# Robot_Psoc.net
KiCad netlist of a schematic drawn in EAGLE
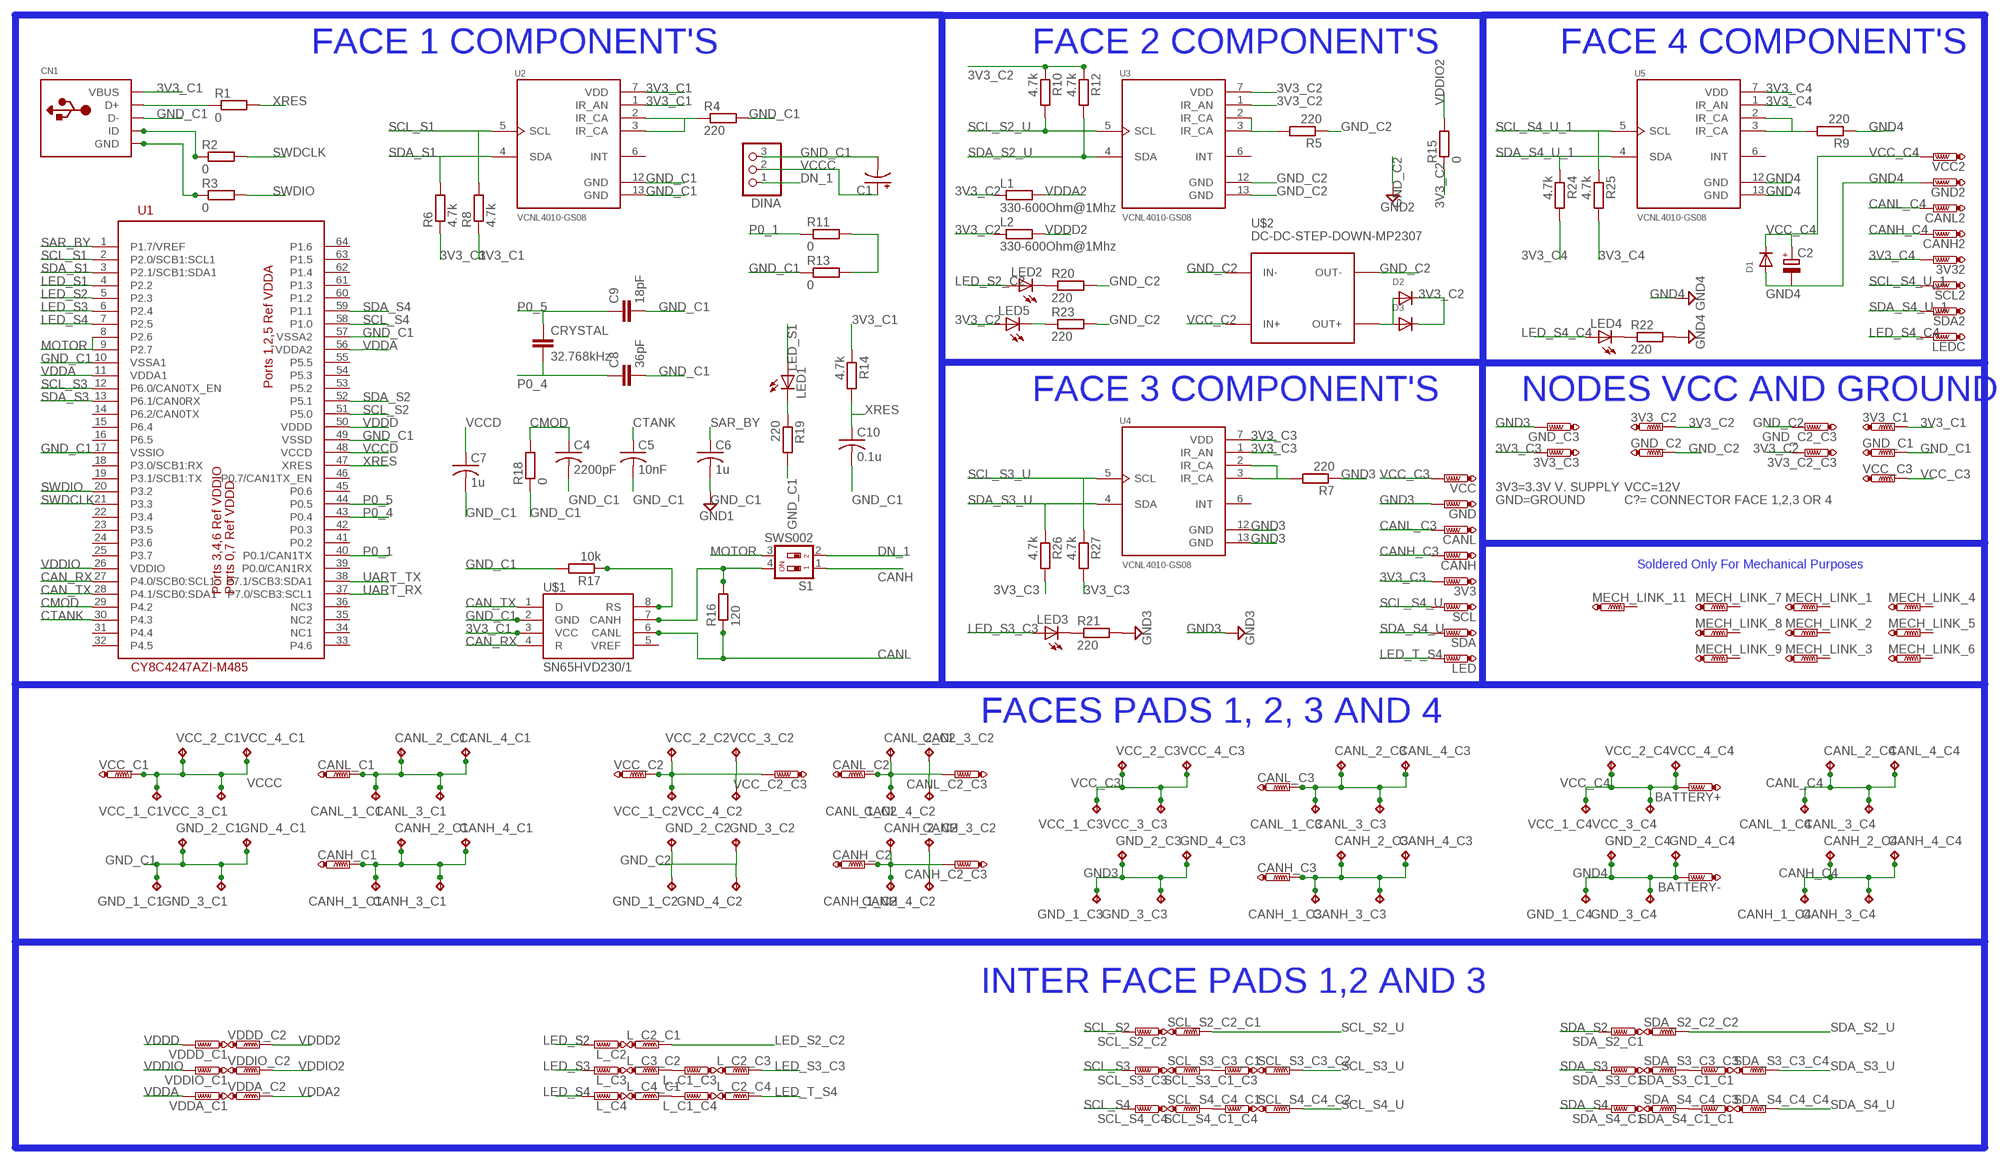
[diagram p0: schematic, sheet 1]

(export (version "E")
  (design (tool "Eeschema 10.0.6"))
  (components
    (comp (ref "3V3")
      (value "PTR1TP11R")
      (footprint "eagle-import:TP11R")
      (libsource (lib "eagle-import") (part "PTR1TP11R"))
    )
    (comp (ref "3V3_C1")
      (value "PTR1TP11R")
      (footprint "eagle-import:TP11R")
      (libsource (lib "eagle-import") (part "PTR1TP11R"))
    )
    (comp (ref "3V3_C2")
      (value "PTR1TP11R")
      (footprint "eagle-import:TP11R")
      (libsource (lib "eagle-import") (part "PTR1TP11R"))
    )
    (comp (ref "3V3_C2_C3")
      (value "PTR1TP11R")
      (footprint "eagle-import:TP11R")
      (libsource (lib "eagle-import") (part "PTR1TP11R"))
    )
    (comp (ref "3V3_C3")
      (value "PTR1TP11R")
      (footprint "eagle-import:TP11R")
      (libsource (lib "eagle-import") (part "PTR1TP11R"))
    )
    (comp (ref "3V32")
      (value "PTR1TP11R")
      (footprint "eagle-import:TP11R")
      (libsource (lib "eagle-import") (part "PTR1TP11R"))
    )
    (comp (ref "BATTERY+")
      (value "PTR1TP11R")
      (footprint "eagle-import:TP11R")
      (libsource (lib "eagle-import") (part "PTR1TP11R"))
    )
    (comp (ref "BATTERY-")
      (value "PTR1TP11R")
      (footprint "eagle-import:TP11R")
      (libsource (lib "eagle-import") (part "PTR1TP11R"))
    )
    (comp (ref "C1")
      (value "CPOL-USUD-5X5,8")
      (footprint "eagle-import:UD-5X5,8_NICHICON")
      (libsource (lib "eagle-import") (part "CPOL-USUD-5X5,8"))
    )
    (comp (ref "C2")
      (value "CPOL-EUUD-8X10")
      (footprint "eagle-import:UD-8X10_NICHICON")
      (libsource (lib "eagle-import") (part "CPOL-EUUD-8X10"))
    )
    (comp (ref "C4")
      (value "2200pF")
      (footprint "eagle-import:C0805")
      (libsource (lib "eagle-import") (part "C-USC0805"))
    )
    (comp (ref "C5")
      (value "10nF")
      (footprint "eagle-import:C0805")
      (libsource (lib "eagle-import") (part "C-USC0805"))
    )
    (comp (ref "C6")
      (value "1u")
      (footprint "eagle-import:C0805")
      (libsource (lib "eagle-import") (part "C-USC0805"))
    )
    (comp (ref "C7")
      (value "1u")
      (footprint "eagle-import:C0805")
      (libsource (lib "eagle-import") (part "C-USC0805"))
    )
    (comp (ref "C8")
      (value "36pF")
      (footprint "eagle-import:C0805")
      (libsource (lib "eagle-import") (part "C-EUC0805"))
    )
    (comp (ref "C9")
      (value "18pF")
      (footprint "eagle-import:C0805")
      (libsource (lib "eagle-import") (part "C-EUC0805"))
    )
    (comp (ref "C10")
      (value "0.1u")
      (footprint "eagle-import:C0805")
      (libsource (lib "eagle-import") (part "C-USC0805"))
    )
    (comp (ref "CANH")
      (value "PTR1TP11R")
      (footprint "eagle-import:TP11R")
      (libsource (lib "eagle-import") (part "PTR1TP11R"))
    )
    (comp (ref "CANH2")
      (value "PTR1TP11R")
      (footprint "eagle-import:TP11R")
      (libsource (lib "eagle-import") (part "PTR1TP11R"))
    )
    (comp (ref "CANH_1_C1")
      (value "TPB2,54")
      (footprint "eagle-import:B2,54")
      (libsource (lib "eagle-import") (part "TPB2,54"))
    )
    (comp (ref "CANH_1_C2")
      (value "TPB2,54")
      (footprint "eagle-import:B2,54")
      (libsource (lib "eagle-import") (part "TPB2,54"))
    )
    (comp (ref "CANH_1_C3")
      (value "TPB2,54")
      (footprint "eagle-import:B2,54")
      (libsource (lib "eagle-import") (part "TPB2,54"))
    )
    (comp (ref "CANH_1_C4")
      (value "TPB2,54")
      (footprint "eagle-import:B2,54")
      (libsource (lib "eagle-import") (part "TPB2,54"))
    )
    (comp (ref "CANH_2_C1")
      (value "TPB2,54")
      (footprint "eagle-import:B2,54")
      (libsource (lib "eagle-import") (part "TPB2,54"))
    )
    (comp (ref "CANH_2_C2")
      (value "TPB2,54")
      (footprint "eagle-import:B2,54")
      (libsource (lib "eagle-import") (part "TPB2,54"))
    )
    (comp (ref "CANH_2_C3")
      (value "TPB2,54")
      (footprint "eagle-import:B2,54")
      (libsource (lib "eagle-import") (part "TPB2,54"))
    )
    (comp (ref "CANH_2_C4")
      (value "TPB2,54")
      (footprint "eagle-import:B2,54")
      (libsource (lib "eagle-import") (part "TPB2,54"))
    )
    (comp (ref "CANH_3_C1")
      (value "TPB2,54")
      (footprint "eagle-import:B2,54")
      (libsource (lib "eagle-import") (part "TPB2,54"))
    )
    (comp (ref "CANH_3_C2")
      (value "TPB2,54")
      (footprint "eagle-import:B2,54")
      (libsource (lib "eagle-import") (part "TPB2,54"))
    )
    (comp (ref "CANH_3_C3")
      (value "TPB2,54")
      (footprint "eagle-import:B2,54")
      (libsource (lib "eagle-import") (part "TPB2,54"))
    )
    (comp (ref "CANH_3_C4")
      (value "TPB2,54")
      (footprint "eagle-import:B2,54")
      (libsource (lib "eagle-import") (part "TPB2,54"))
    )
    (comp (ref "CANH_4_C1")
      (value "TPB2,54")
      (footprint "eagle-import:B2,54")
      (libsource (lib "eagle-import") (part "TPB2,54"))
    )
    (comp (ref "CANH_4_C2")
      (value "TPB2,54")
      (footprint "eagle-import:B2,54")
      (libsource (lib "eagle-import") (part "TPB2,54"))
    )
    (comp (ref "CANH_4_C3")
      (value "TPB2,54")
      (footprint "eagle-import:B2,54")
      (libsource (lib "eagle-import") (part "TPB2,54"))
    )
    (comp (ref "CANH_4_C4")
      (value "TPB2,54")
      (footprint "eagle-import:B2,54")
      (libsource (lib "eagle-import") (part "TPB2,54"))
    )
    (comp (ref "CANH_C1")
      (value "PTR1TP11R")
      (footprint "eagle-import:TP11R")
      (libsource (lib "eagle-import") (part "PTR1TP11R"))
    )
    (comp (ref "CANH_C2")
      (value "PTR1TP11R")
      (footprint "eagle-import:TP11R")
      (libsource (lib "eagle-import") (part "PTR1TP11R"))
    )
    (comp (ref "CANH_C2_C3")
      (value "PTR1TP11R")
      (footprint "eagle-import:TP11R")
      (libsource (lib "eagle-import") (part "PTR1TP11R"))
    )
    (comp (ref "CANH_C3")
      (value "PTR1TP11R")
      (footprint "eagle-import:TP11R")
      (libsource (lib "eagle-import") (part "PTR1TP11R"))
    )
    (comp (ref "CANL")
      (value "PTR1TP11R")
      (footprint "eagle-import:TP11R")
      (libsource (lib "eagle-import") (part "PTR1TP11R"))
    )
    (comp (ref "CANL2")
      (value "PTR1TP11R")
      (footprint "eagle-import:TP11R")
      (libsource (lib "eagle-import") (part "PTR1TP11R"))
    )
    (comp (ref "CANL_1_C1")
      (value "TPB2,54")
      (footprint "eagle-import:B2,54")
      (libsource (lib "eagle-import") (part "TPB2,54"))
    )
    (comp (ref "CANL_1_C2")
      (value "TPB2,54")
      (footprint "eagle-import:B2,54")
      (libsource (lib "eagle-import") (part "TPB2,54"))
    )
    (comp (ref "CANL_1_C3")
      (value "TPB2,54")
      (footprint "eagle-import:B2,54")
      (libsource (lib "eagle-import") (part "TPB2,54"))
    )
    (comp (ref "CANL_1_C4")
      (value "TPB2,54")
      (footprint "eagle-import:B2,54")
      (libsource (lib "eagle-import") (part "TPB2,54"))
    )
    (comp (ref "CANL_2_C1")
      (value "TPB2,54")
      (footprint "eagle-import:B2,54")
      (libsource (lib "eagle-import") (part "TPB2,54"))
    )
    (comp (ref "CANL_2_C2")
      (value "TPB2,54")
      (footprint "eagle-import:B2,54")
      (libsource (lib "eagle-import") (part "TPB2,54"))
    )
    (comp (ref "CANL_2_C3")
      (value "TPB2,54")
      (footprint "eagle-import:B2,54")
      (libsource (lib "eagle-import") (part "TPB2,54"))
    )
    (comp (ref "CANL_2_C4")
      (value "TPB2,54")
      (footprint "eagle-import:B2,54")
      (libsource (lib "eagle-import") (part "TPB2,54"))
    )
    (comp (ref "CANL_3_C1")
      (value "TPB2,54")
      (footprint "eagle-import:B2,54")
      (libsource (lib "eagle-import") (part "TPB2,54"))
    )
    (comp (ref "CANL_3_C2")
      (value "TPB2,54")
      (footprint "eagle-import:B2,54")
      (libsource (lib "eagle-import") (part "TPB2,54"))
    )
    (comp (ref "CANL_3_C3")
      (value "TPB2,54")
      (footprint "eagle-import:B2,54")
      (libsource (lib "eagle-import") (part "TPB2,54"))
    )
    (comp (ref "CANL_3_C4")
      (value "TPB2,54")
      (footprint "eagle-import:B2,54")
      (libsource (lib "eagle-import") (part "TPB2,54"))
    )
    (comp (ref "CANL_4_C1")
      (value "TPB2,54")
      (footprint "eagle-import:B2,54")
      (libsource (lib "eagle-import") (part "TPB2,54"))
    )
    (comp (ref "CANL_4_C2")
      (value "TPB2,54")
      (footprint "eagle-import:B2,54")
      (libsource (lib "eagle-import") (part "TPB2,54"))
    )
    (comp (ref "CANL_4_C3")
      (value "TPB2,54")
      (footprint "eagle-import:B2,54")
      (libsource (lib "eagle-import") (part "TPB2,54"))
    )
    (comp (ref "CANL_4_C4")
      (value "TPB2,54")
      (footprint "eagle-import:B2,54")
      (libsource (lib "eagle-import") (part "TPB2,54"))
    )
    (comp (ref "CANL_C1")
      (value "PTR1TP11R")
      (footprint "eagle-import:TP11R")
      (libsource (lib "eagle-import") (part "PTR1TP11R"))
    )
    (comp (ref "CANL_C2")
      (value "PTR1TP11R")
      (footprint "eagle-import:TP11R")
      (libsource (lib "eagle-import") (part "PTR1TP11R"))
    )
    (comp (ref "CANL_C2_C3")
      (value "PTR1TP11R")
      (footprint "eagle-import:TP11R")
      (libsource (lib "eagle-import") (part "PTR1TP11R"))
    )
    (comp (ref "CANL_C3")
      (value "PTR1TP11R")
      (footprint "eagle-import:TP11R")
      (libsource (lib "eagle-import") (part "PTR1TP11R"))
    )
    (comp (ref "CN1")
      (value "USBMINIB")
      (footprint "eagle-import:USB-MINIB")
      (libsource (lib "eagle-import") (part "USBMINIB"))
    )
    (comp (ref "CRYSTAL")
      (value "32.768kHz")
      (footprint "eagle-import:C0603")
      (libsource (lib "eagle-import") (part "C-EUC0603"))
    )
    (comp (ref "D1")
      (value "DIODESMA")
      (footprint "eagle-import:SMADIODE")
      (libsource (lib "eagle-import") (part "DIODESMA"))
    )
    (comp (ref "D2")
      (value "DIODESOD-123")
      (footprint "eagle-import:SOD-123")
      (libsource (lib "eagle-import") (part "DIODESOD-123"))
    )
    (comp (ref "D3")
      (value "DIODESOD-123")
      (footprint "eagle-import:SOD-123")
      (libsource (lib "eagle-import") (part "DIODESOD-123"))
    )
    (comp (ref "DINA")
      (value "PINHD-1X3")
      (footprint "eagle-import:1X03")
      (libsource (lib "eagle-import") (part "PINHD-1X3"))
    )
    (comp (ref "GND")
      (value "PTR1TP11R")
      (footprint "eagle-import:TP11R")
      (libsource (lib "eagle-import") (part "PTR1TP11R"))
    )
    (comp (ref "GND2")
      (value "PTR1TP11R")
      (footprint "eagle-import:TP11R")
      (libsource (lib "eagle-import") (part "PTR1TP11R"))
    )
    (comp (ref "GND_1_C1")
      (value "TPB2,54")
      (footprint "eagle-import:B2,54")
      (libsource (lib "eagle-import") (part "TPB2,54"))
    )
    (comp (ref "GND_1_C2")
      (value "TPB2,54")
      (footprint "eagle-import:B2,54")
      (libsource (lib "eagle-import") (part "TPB2,54"))
    )
    (comp (ref "GND_1_C3")
      (value "TPB2,54")
      (footprint "eagle-import:B2,54")
      (libsource (lib "eagle-import") (part "TPB2,54"))
    )
    (comp (ref "GND_1_C4")
      (value "TPB2,54")
      (footprint "eagle-import:B2,54")
      (libsource (lib "eagle-import") (part "TPB2,54"))
    )
    (comp (ref "GND_2_C1")
      (value "TPB2,54")
      (footprint "eagle-import:B2,54")
      (libsource (lib "eagle-import") (part "TPB2,54"))
    )
    (comp (ref "GND_2_C2")
      (value "TPB2,54")
      (footprint "eagle-import:B2,54")
      (libsource (lib "eagle-import") (part "TPB2,54"))
    )
    (comp (ref "GND_2_C3")
      (value "TPB2,54")
      (footprint "eagle-import:B2,54")
      (libsource (lib "eagle-import") (part "TPB2,54"))
    )
    (comp (ref "GND_2_C4")
      (value "TPB2,54")
      (footprint "eagle-import:B2,54")
      (libsource (lib "eagle-import") (part "TPB2,54"))
    )
    (comp (ref "GND_3_C1")
      (value "TPB2,54")
      (footprint "eagle-import:B2,54")
      (libsource (lib "eagle-import") (part "TPB2,54"))
    )
    (comp (ref "GND_3_C2")
      (value "TPB2,54")
      (footprint "eagle-import:B2,54")
      (libsource (lib "eagle-import") (part "TPB2,54"))
    )
    (comp (ref "GND_3_C3")
      (value "TPB2,54")
      (footprint "eagle-import:B2,54")
      (libsource (lib "eagle-import") (part "TPB2,54"))
    )
    (comp (ref "GND_3_C4")
      (value "TPB2,54")
      (footprint "eagle-import:B2,54")
      (libsource (lib "eagle-import") (part "TPB2,54"))
    )
    (comp (ref "GND_4_C1")
      (value "TPB2,54")
      (footprint "eagle-import:B2,54")
      (libsource (lib "eagle-import") (part "TPB2,54"))
    )
    (comp (ref "GND_4_C2")
      (value "TPB2,54")
      (footprint "eagle-import:B2,54")
      (libsource (lib "eagle-import") (part "TPB2,54"))
    )
    (comp (ref "GND_4_C3")
      (value "TPB2,54")
      (footprint "eagle-import:B2,54")
      (libsource (lib "eagle-import") (part "TPB2,54"))
    )
    (comp (ref "GND_4_C4")
      (value "TPB2,54")
      (footprint "eagle-import:B2,54")
      (libsource (lib "eagle-import") (part "TPB2,54"))
    )
    (comp (ref "GND_C1")
      (value "PTR1TP11R")
      (footprint "eagle-import:TP11R")
      (libsource (lib "eagle-import") (part "PTR1TP11R"))
    )
    (comp (ref "GND_C2")
      (value "PTR1TP11R")
      (footprint "eagle-import:TP11R")
      (libsource (lib "eagle-import") (part "PTR1TP11R"))
    )
    (comp (ref "GND_C2_C3")
      (value "PTR1TP11R")
      (footprint "eagle-import:TP11R")
      (libsource (lib "eagle-import") (part "PTR1TP11R"))
    )
    (comp (ref "GND_C3")
      (value "PTR1TP11R")
      (footprint "eagle-import:TP11R")
      (libsource (lib "eagle-import") (part "PTR1TP11R"))
    )
    (comp (ref "L1")
      (value "330-600Ohm@1Mhz")
      (footprint "eagle-import:R0805")
      (libsource (lib "eagle-import") (part "R-EU_R0805"))
    )
    (comp (ref "L2")
      (value "330-600Ohm@1Mhz")
      (footprint "eagle-import:R0805")
      (libsource (lib "eagle-import") (part "R-EU_R0805"))
    )
    (comp (ref "LED")
      (value "PTR1TP11R")
      (footprint "eagle-import:TP11R")
      (libsource (lib "eagle-import") (part "PTR1TP11R"))
    )
    (comp (ref "LED1")
      (value "LEDCHIPLED_0805")
      (footprint "eagle-import:CHIPLED_0805")
      (libsource (lib "eagle-import") (part "LEDCHIPLED_0805"))
    )
    (comp (ref "LED2")
      (value "LEDCHIPLED_0805")
      (footprint "eagle-import:CHIPLED_0805")
      (libsource (lib "eagle-import") (part "LEDCHIPLED_0805"))
    )
    (comp (ref "LED3")
      (value "LEDCHIPLED_0805")
      (footprint "eagle-import:CHIPLED_0805")
      (libsource (lib "eagle-import") (part "LEDCHIPLED_0805"))
    )
    (comp (ref "LED4")
      (value "LEDCHIPLED_0805")
      (footprint "eagle-import:CHIPLED_0805")
      (libsource (lib "eagle-import") (part "LEDCHIPLED_0805"))
    )
    (comp (ref "LED5")
      (value "LEDCHIPLED_0805")
      (footprint "eagle-import:CHIPLED_0805")
      (libsource (lib "eagle-import") (part "LEDCHIPLED_0805"))
    )
    (comp (ref "LEDC")
      (value "PTR1TP11R")
      (footprint "eagle-import:TP11R")
      (libsource (lib "eagle-import") (part "PTR1TP11R"))
    )
    (comp (ref "L_C1_C3")
      (value "PTR1TP11R")
      (footprint "eagle-import:TP11R")
      (libsource (lib "eagle-import") (part "PTR1TP11R"))
    )
    (comp (ref "L_C1_C4")
      (value "PTR1TP11R")
      (footprint "eagle-import:TP11R")
      (libsource (lib "eagle-import") (part "PTR1TP11R"))
    )
    (comp (ref "L_C2")
      (value "PTR1TP11R")
      (footprint "eagle-import:TP11R")
      (libsource (lib "eagle-import") (part "PTR1TP11R"))
    )
    (comp (ref "L_C2_C1")
      (value "PTR1TP11R")
      (footprint "eagle-import:TP11R")
      (libsource (lib "eagle-import") (part "PTR1TP11R"))
    )
    (comp (ref "L_C2_C3")
      (value "PTR1TP11R")
      (footprint "eagle-import:TP11R")
      (libsource (lib "eagle-import") (part "PTR1TP11R"))
    )
    (comp (ref "L_C2_C4")
      (value "PTR1TP11R")
      (footprint "eagle-import:TP11R")
      (libsource (lib "eagle-import") (part "PTR1TP11R"))
    )
    (comp (ref "L_C3")
      (value "PTR1TP11R")
      (footprint "eagle-import:TP11R")
      (libsource (lib "eagle-import") (part "PTR1TP11R"))
    )
    (comp (ref "L_C3_C2")
      (value "PTR1TP11R")
      (footprint "eagle-import:TP11R")
      (libsource (lib "eagle-import") (part "PTR1TP11R"))
    )
    (comp (ref "L_C4")
      (value "PTR1TP11R")
      (footprint "eagle-import:TP11R")
      (libsource (lib "eagle-import") (part "PTR1TP11R"))
    )
    (comp (ref "L_C4_C1")
      (value "PTR1TP11R")
      (footprint "eagle-import:TP11R")
      (libsource (lib "eagle-import") (part "PTR1TP11R"))
    )
    (comp (ref "MECH_LINK_1")
      (value "PTR1TP11R")
      (footprint "eagle-import:TP11R")
      (libsource (lib "eagle-import") (part "PTR1TP11R"))
    )
    (comp (ref "MECH_LINK_2")
      (value "PTR1TP11R")
      (footprint "eagle-import:TP11R")
      (libsource (lib "eagle-import") (part "PTR1TP11R"))
    )
    (comp (ref "MECH_LINK_3")
      (value "PTR1TP11R")
      (footprint "eagle-import:TP11R")
      (libsource (lib "eagle-import") (part "PTR1TP11R"))
    )
    (comp (ref "MECH_LINK_4")
      (value "PTR1TP11R")
      (footprint "eagle-import:TP11R")
      (libsource (lib "eagle-import") (part "PTR1TP11R"))
    )
    (comp (ref "MECH_LINK_5")
      (value "PTR1TP11R")
      (footprint "eagle-import:TP11R")
      (libsource (lib "eagle-import") (part "PTR1TP11R"))
    )
    (comp (ref "MECH_LINK_6")
      (value "PTR1TP11R")
      (footprint "eagle-import:TP11R")
      (libsource (lib "eagle-import") (part "PTR1TP11R"))
    )
    (comp (ref "MECH_LINK_7")
      (value "PTR1TP11R")
      (footprint "eagle-import:TP11R")
      (libsource (lib "eagle-import") (part "PTR1TP11R"))
    )
    (comp (ref "MECH_LINK_8")
      (value "PTR1TP11R")
      (footprint "eagle-import:TP11R")
      (libsource (lib "eagle-import") (part "PTR1TP11R"))
    )
    (comp (ref "MECH_LINK_9")
      (value "PTR1TP11R")
      (footprint "eagle-import:TP11R")
      (libsource (lib "eagle-import") (part "PTR1TP11R"))
    )
    (comp (ref "MECH_LINK_11")
      (value "PTR1TP11R")
      (footprint "eagle-import:TP11R")
      (libsource (lib "eagle-import") (part "PTR1TP11R"))
    )
    (comp (ref "R1")
      (value "0")
      (footprint "eagle-import:R0805")
      (libsource (lib "eagle-import") (part "R-EU_R0805"))
    )
    (comp (ref "R2")
      (value "0")
      (footprint "eagle-import:R0805")
      (libsource (lib "eagle-import") (part "R-EU_R0805"))
    )
    (comp (ref "R3")
      (value "0")
      (footprint "eagle-import:R0805")
      (libsource (lib "eagle-import") (part "R-EU_R0805"))
    )
    (comp (ref "R4")
      (value "220")
      (footprint "eagle-import:R0805")
      (libsource (lib "eagle-import") (part "R-EU_R0805"))
    )
    (comp (ref "R5")
      (value "220")
      (footprint "eagle-import:R0805")
      (libsource (lib "eagle-import") (part "R-EU_R0805"))
    )
    (comp (ref "R6")
      (value "4.7k")
      (footprint "eagle-import:R0805")
      (libsource (lib "eagle-import") (part "R-EU_R0805"))
    )
    (comp (ref "R7")
      (value "220")
      (footprint "eagle-import:R0805")
      (libsource (lib "eagle-import") (part "R-EU_R0805"))
    )
    (comp (ref "R8")
      (value "4.7k")
      (footprint "eagle-import:R0805")
      (libsource (lib "eagle-import") (part "R-EU_R0805"))
    )
    (comp (ref "R9")
      (value "220")
      (footprint "eagle-import:R0805")
      (libsource (lib "eagle-import") (part "R-EU_R0805"))
    )
    (comp (ref "R10")
      (value "4.7k")
      (footprint "eagle-import:R0805")
      (libsource (lib "eagle-import") (part "R-EU_R0805"))
    )
    (comp (ref "R11")
      (value "0")
      (footprint "eagle-import:R0805")
      (libsource (lib "eagle-import") (part "R-EU_R0805"))
    )
    (comp (ref "R12")
      (value "4.7k")
      (footprint "eagle-import:R0805")
      (libsource (lib "eagle-import") (part "R-EU_R0805"))
    )
    (comp (ref "R13")
      (value "0")
      (footprint "eagle-import:R0805")
      (libsource (lib "eagle-import") (part "R-EU_R0805"))
    )
    (comp (ref "R14")
      (value "4.7k")
      (footprint "eagle-import:R0805")
      (libsource (lib "eagle-import") (part "R-EU_R0805"))
    )
    (comp (ref "R15")
      (value "0")
      (footprint "eagle-import:R0805")
      (libsource (lib "eagle-import") (part "R-EU_R0805"))
    )
    (comp (ref "R16")
      (value "120")
      (footprint "eagle-import:R0805")
      (libsource (lib "eagle-import") (part "R-EU_R0805"))
    )
    (comp (ref "R17")
      (value "10k")
      (footprint "eagle-import:R0805")
      (libsource (lib "eagle-import") (part "R-EU_R0805"))
    )
    (comp (ref "R18")
      (value "0")
      (footprint "eagle-import:R0805")
      (libsource (lib "eagle-import") (part "R-EU_R0805"))
    )
    (comp (ref "R19")
      (value "220")
      (footprint "eagle-import:R0805")
      (libsource (lib "eagle-import") (part "R-EU_R0805"))
    )
    (comp (ref "R20")
      (value "220")
      (footprint "eagle-import:R0805")
      (libsource (lib "eagle-import") (part "R-EU_R0805"))
    )
    (comp (ref "R21")
      (value "220")
      (footprint "eagle-import:R0805")
      (libsource (lib "eagle-import") (part "R-EU_R0805"))
    )
    (comp (ref "R22")
      (value "220")
      (footprint "eagle-import:R0805")
      (libsource (lib "eagle-import") (part "R-EU_R0805"))
    )
    (comp (ref "R23")
      (value "220")
      (footprint "eagle-import:R0805")
      (libsource (lib "eagle-import") (part "R-EU_R0805"))
    )
    (comp (ref "R24")
      (value "4.7k")
      (footprint "eagle-import:R0805")
      (libsource (lib "eagle-import") (part "R-EU_R0805"))
    )
    (comp (ref "R25")
      (value "4.7k")
      (footprint "eagle-import:R0805")
      (libsource (lib "eagle-import") (part "R-EU_R0805"))
    )
    (comp (ref "R26")
      (value "4.7k")
      (footprint "eagle-import:R0805")
      (libsource (lib "eagle-import") (part "R-EU_R0805"))
    )
    (comp (ref "R27")
      (value "4.7k")
      (footprint "eagle-import:R0805")
      (libsource (lib "eagle-import") (part "R-EU_R0805"))
    )
    (comp (ref "S1")
      (value "SWS002")
      (footprint "eagle-import:SMS-002")
      (libsource (lib "eagle-import") (part "SWS002"))
    )
    (comp (ref "SCL")
      (value "PTR1TP11R")
      (footprint "eagle-import:TP11R")
      (libsource (lib "eagle-import") (part "PTR1TP11R"))
    )
    (comp (ref "SCL2")
      (value "PTR1TP11R")
      (footprint "eagle-import:TP11R")
      (libsource (lib "eagle-import") (part "PTR1TP11R"))
    )
    (comp (ref "SCL_S2_C2")
      (value "PTR1TP11R")
      (footprint "eagle-import:TP11R")
      (libsource (lib "eagle-import") (part "PTR1TP11R"))
    )
    (comp (ref "SCL_S2_C2_C1")
      (value "PTR1TP11R")
      (footprint "eagle-import:TP11R")
      (libsource (lib "eagle-import") (part "PTR1TP11R"))
    )
    (comp (ref "SCL_S3_C1_C3")
      (value "PTR1TP11R")
      (footprint "eagle-import:TP11R")
      (libsource (lib "eagle-import") (part "PTR1TP11R"))
    )
    (comp (ref "SCL_S3_C3")
      (value "PTR1TP11R")
      (footprint "eagle-import:TP11R")
      (libsource (lib "eagle-import") (part "PTR1TP11R"))
    )
    (comp (ref "SCL_S3_C3_C1")
      (value "PTR1TP11R")
      (footprint "eagle-import:TP11R")
      (libsource (lib "eagle-import") (part "PTR1TP11R"))
    )
    (comp (ref "SCL_S3_C3_C2")
      (value "PTR1TP11R")
      (footprint "eagle-import:TP11R")
      (libsource (lib "eagle-import") (part "PTR1TP11R"))
    )
    (comp (ref "SCL_S4_C1_C4")
      (value "PTR1TP11R")
      (footprint "eagle-import:TP11R")
      (libsource (lib "eagle-import") (part "PTR1TP11R"))
    )
    (comp (ref "SCL_S4_C4")
      (value "PTR1TP11R")
      (footprint "eagle-import:TP11R")
      (libsource (lib "eagle-import") (part "PTR1TP11R"))
    )
    (comp (ref "SCL_S4_C4_C1")
      (value "PTR1TP11R")
      (footprint "eagle-import:TP11R")
      (libsource (lib "eagle-import") (part "PTR1TP11R"))
    )
    (comp (ref "SCL_S4_C4_C2")
      (value "PTR1TP11R")
      (footprint "eagle-import:TP11R")
      (libsource (lib "eagle-import") (part "PTR1TP11R"))
    )
    (comp (ref "SDA")
      (value "PTR1TP11R")
      (footprint "eagle-import:TP11R")
      (libsource (lib "eagle-import") (part "PTR1TP11R"))
    )
    (comp (ref "SDA2")
      (value "PTR1TP11R")
      (footprint "eagle-import:TP11R")
      (libsource (lib "eagle-import") (part "PTR1TP11R"))
    )
    (comp (ref "SDA_S2_C1")
      (value "PTR1TP11R")
      (footprint "eagle-import:TP11R")
      (libsource (lib "eagle-import") (part "PTR1TP11R"))
    )
    (comp (ref "SDA_S2_C2_C2")
      (value "PTR1TP11R")
      (footprint "eagle-import:TP11R")
      (libsource (lib "eagle-import") (part "PTR1TP11R"))
    )
    (comp (ref "SDA_S3_C1")
      (value "PTR1TP11R")
      (footprint "eagle-import:TP11R")
      (libsource (lib "eagle-import") (part "PTR1TP11R"))
    )
    (comp (ref "SDA_S3_C1_C1")
      (value "PTR1TP11R")
      (footprint "eagle-import:TP11R")
      (libsource (lib "eagle-import") (part "PTR1TP11R"))
    )
    (comp (ref "SDA_S3_C3_C3")
      (value "PTR1TP11R")
      (footprint "eagle-import:TP11R")
      (libsource (lib "eagle-import") (part "PTR1TP11R"))
    )
    (comp (ref "SDA_S3_C3_C4")
      (value "PTR1TP11R")
      (footprint "eagle-import:TP11R")
      (libsource (lib "eagle-import") (part "PTR1TP11R"))
    )
    (comp (ref "SDA_S4_C1")
      (value "PTR1TP11R")
      (footprint "eagle-import:TP11R")
      (libsource (lib "eagle-import") (part "PTR1TP11R"))
    )
    (comp (ref "SDA_S4_C1_C1")
      (value "PTR1TP11R")
      (footprint "eagle-import:TP11R")
      (libsource (lib "eagle-import") (part "PTR1TP11R"))
    )
    (comp (ref "SDA_S4_C4_C3")
      (value "PTR1TP11R")
      (footprint "eagle-import:TP11R")
      (libsource (lib "eagle-import") (part "PTR1TP11R"))
    )
    (comp (ref "SDA_S4_C4_C4")
      (value "PTR1TP11R")
      (footprint "eagle-import:TP11R")
      (libsource (lib "eagle-import") (part "PTR1TP11R"))
    )
    (comp (ref "U$1")
      (value "SN65HVD230/1")
      (footprint "eagle-import:SO8")
      (libsource (lib "eagle-import") (part "SN65HVD230/1"))
    )
    (comp (ref "U$2")
      (value "DC-DC-STEP-DOWN-MP2307")
      (footprint "eagle-import:DC-DC-STEP-DOWN-MP2307")
      (libsource (lib "eagle-import") (part "DC-DC-STEP-DOWN-MP2307"))
    )
    (comp (ref "U1")
      (value "CY8C4247AZI-M485")
      (footprint "eagle-import:TQFP64-10X10")
      (libsource (lib "eagle-import") (part "CY8C4247AZI-M485"))
    )
    (comp (ref "U2")
      (value "VCNL4010-GS08")
      (footprint "eagle-import:XDCR_VCNL4010-GS08")
      (libsource (lib "eagle-import") (part "VCNL4010-GS08"))
    )
    (comp (ref "U3")
      (value "VCNL4010-GS08")
      (footprint "eagle-import:XDCR_VCNL4010-GS08")
      (libsource (lib "eagle-import") (part "VCNL4010-GS08"))
    )
    (comp (ref "U4")
      (value "VCNL4010-GS08")
      (footprint "eagle-import:XDCR_VCNL4010-GS08")
      (libsource (lib "eagle-import") (part "VCNL4010-GS08"))
    )
    (comp (ref "U5")
      (value "VCNL4010-GS08")
      (footprint "eagle-import:XDCR_VCNL4010-GS08")
      (libsource (lib "eagle-import") (part "VCNL4010-GS08"))
    )
    (comp (ref "VCC")
      (value "PTR1TP11R")
      (footprint "eagle-import:TP11R")
      (libsource (lib "eagle-import") (part "PTR1TP11R"))
    )
    (comp (ref "VCC2")
      (value "PTR1TP11R")
      (footprint "eagle-import:TP11R")
      (libsource (lib "eagle-import") (part "PTR1TP11R"))
    )
    (comp (ref "VCC_1_C1")
      (value "TPB2,54")
      (footprint "eagle-import:B2,54")
      (libsource (lib "eagle-import") (part "TPB2,54"))
    )
    (comp (ref "VCC_1_C2")
      (value "TPB2,54")
      (footprint "eagle-import:B2,54")
      (libsource (lib "eagle-import") (part "TPB2,54"))
    )
    (comp (ref "VCC_1_C3")
      (value "TPB2,54")
      (footprint "eagle-import:B2,54")
      (libsource (lib "eagle-import") (part "TPB2,54"))
    )
    (comp (ref "VCC_1_C4")
      (value "TPB2,54")
      (footprint "eagle-import:B2,54")
      (libsource (lib "eagle-import") (part "TPB2,54"))
    )
    (comp (ref "VCC_2_C1")
      (value "TPB2,54")
      (footprint "eagle-import:B2,54")
      (libsource (lib "eagle-import") (part "TPB2,54"))
    )
    (comp (ref "VCC_2_C2")
      (value "TPB2,54")
      (footprint "eagle-import:B2,54")
      (libsource (lib "eagle-import") (part "TPB2,54"))
    )
    (comp (ref "VCC_2_C3")
      (value "TPB2,54")
      (footprint "eagle-import:B2,54")
      (libsource (lib "eagle-import") (part "TPB2,54"))
    )
    (comp (ref "VCC_2_C4")
      (value "TPB2,54")
      (footprint "eagle-import:B2,54")
      (libsource (lib "eagle-import") (part "TPB2,54"))
    )
    (comp (ref "VCC_3_C1")
      (value "TPB2,54")
      (footprint "eagle-import:B2,54")
      (libsource (lib "eagle-import") (part "TPB2,54"))
    )
    (comp (ref "VCC_3_C2")
      (value "TPB2,54")
      (footprint "eagle-import:B2,54")
      (libsource (lib "eagle-import") (part "TPB2,54"))
    )
    (comp (ref "VCC_3_C3")
      (value "TPB2,54")
      (footprint "eagle-import:B2,54")
      (libsource (lib "eagle-import") (part "TPB2,54"))
    )
    (comp (ref "VCC_3_C4")
      (value "TPB2,54")
      (footprint "eagle-import:B2,54")
      (libsource (lib "eagle-import") (part "TPB2,54"))
    )
    (comp (ref "VCC_4_C1")
      (value "TPB2,54")
      (footprint "eagle-import:B2,54")
      (libsource (lib "eagle-import") (part "TPB2,54"))
    )
    (comp (ref "VCC_4_C2")
      (value "TPB2,54")
      (footprint "eagle-import:B2,54")
      (libsource (lib "eagle-import") (part "TPB2,54"))
    )
    (comp (ref "VCC_4_C3")
      (value "TPB2,54")
      (footprint "eagle-import:B2,54")
      (libsource (lib "eagle-import") (part "TPB2,54"))
    )
    (comp (ref "VCC_4_C4")
      (value "TPB2,54")
      (footprint "eagle-import:B2,54")
      (libsource (lib "eagle-import") (part "TPB2,54"))
    )
    (comp (ref "VCC_C1")
      (value "PTR1TP11R")
      (footprint "eagle-import:TP11R")
      (libsource (lib "eagle-import") (part "PTR1TP11R"))
    )
    (comp (ref "VCC_C2")
      (value "PTR1TP11R")
      (footprint "eagle-import:TP11R")
      (libsource (lib "eagle-import") (part "PTR1TP11R"))
    )
    (comp (ref "VCC_C2_C3")
      (value "PTR1TP11R")
      (footprint "eagle-import:TP11R")
      (libsource (lib "eagle-import") (part "PTR1TP11R"))
    )
    (comp (ref "VCC_C3")
      (value "PTR1TP11R")
      (footprint "eagle-import:TP11R")
      (libsource (lib "eagle-import") (part "PTR1TP11R"))
    )
    (comp (ref "VDDA_C1")
      (value "PTR1TP11R")
      (footprint "eagle-import:TP11R")
      (libsource (lib "eagle-import") (part "PTR1TP11R"))
    )
    (comp (ref "VDDA_C2")
      (value "PTR1TP11R")
      (footprint "eagle-import:TP11R")
      (libsource (lib "eagle-import") (part "PTR1TP11R"))
    )
    (comp (ref "VDDD_C1")
      (value "PTR1TP11R")
      (footprint "eagle-import:TP11R")
      (libsource (lib "eagle-import") (part "PTR1TP11R"))
    )
    (comp (ref "VDDD_C2")
      (value "PTR1TP11R")
      (footprint "eagle-import:TP11R")
      (libsource (lib "eagle-import") (part "PTR1TP11R"))
    )
    (comp (ref "VDDIO_C1")
      (value "PTR1TP11R")
      (footprint "eagle-import:TP11R")
      (libsource (lib "eagle-import") (part "PTR1TP11R"))
    )
    (comp (ref "VDDIO_C2")
      (value "PTR1TP11R")
      (footprint "eagle-import:TP11R")
      (libsource (lib "eagle-import") (part "PTR1TP11R"))
    )
  )
  (nets
    (net (code "1") (name "/3V3_C1") (class "Default")
      (node (ref "3V3_C1") (pin "TP") (pinfunction "TP_TP") (pintype "input"))
      (node (ref "CN1") (pin "VBUS") (pinfunction "VBUS_VBUS") (pintype "power_in"))
      (node (ref "R14") (pin "1") (pinfunction "1_1") (pintype "passive"))
      (node (ref "R6") (pin "1") (pinfunction "1_1") (pintype "passive"))
      (node (ref "R8") (pin "1") (pinfunction "1_1") (pintype "passive"))
      (node (ref "U$1") (pin "3") (pinfunction "VCC_3") (pintype "power_in"))
      (node (ref "U2") (pin "1") (pinfunction "IR_AN_1") (pintype "power_in"))
      (node (ref "U2") (pin "7") (pinfunction "VDD_7") (pintype "power_in"))
    )
    (net (code "2") (name "/3V3_C2") (class "Default")
      (node (ref "3V3_C2") (pin "TP") (pinfunction "TP_TP") (pintype "input"))
      (node (ref "3V3_C2_C3") (pin "TP") (pinfunction "TP_TP") (pintype "input"))
      (node (ref "D2") (pin "C") (pinfunction "C_C") (pintype "passive"))
      (node (ref "D3") (pin "C") (pinfunction "C_C") (pintype "passive"))
      (node (ref "L1") (pin "1") (pinfunction "1_1") (pintype "passive"))
      (node (ref "L2") (pin "1") (pinfunction "1_1") (pintype "passive"))
      (node (ref "LED5") (pin "A") (pinfunction "A_A") (pintype "passive"))
      (node (ref "R10") (pin "1") (pinfunction "1_1") (pintype "passive"))
      (node (ref "R12") (pin "1") (pinfunction "1_1") (pintype "passive"))
      (node (ref "R15") (pin "1") (pinfunction "1_1") (pintype "passive"))
      (node (ref "U3") (pin "1") (pinfunction "IR_AN_1") (pintype "power_in"))
      (node (ref "U3") (pin "7") (pinfunction "VDD_7") (pintype "power_in"))
    )
    (net (code "3") (name "/3V3_C3") (class "Default")
      (node (ref "3V3") (pin "TP") (pinfunction "TP_TP") (pintype "input"))
      (node (ref "3V3_C3") (pin "TP") (pinfunction "TP_TP") (pintype "input"))
      (node (ref "R26") (pin "2") (pinfunction "2_2") (pintype "passive"))
      (node (ref "R27") (pin "2") (pinfunction "2_2") (pintype "passive"))
      (node (ref "U4") (pin "1") (pinfunction "IR_AN_1") (pintype "power_in"))
      (node (ref "U4") (pin "7") (pinfunction "VDD_7") (pintype "power_in"))
    )
    (net (code "4") (name "/3V3_C4") (class "Default")
      (node (ref "3V32") (pin "TP") (pinfunction "TP_TP") (pintype "input"))
      (node (ref "R24") (pin "2") (pinfunction "2_2") (pintype "passive"))
      (node (ref "R25") (pin "2") (pinfunction "2_2") (pintype "passive"))
      (node (ref "U5") (pin "1") (pinfunction "IR_AN_1") (pintype "power_in"))
      (node (ref "U5") (pin "7") (pinfunction "VDD_7") (pintype "power_in"))
    )
    (net (code "5") (name "/CANH") (class "Default")
      (node (ref "CANH_1_C1") (pin "TP") (pinfunction "TP_TP") (pintype "input"))
      (node (ref "CANH_2_C1") (pin "TP") (pinfunction "TP_TP") (pintype "input"))
      (node (ref "CANH_3_C1") (pin "TP") (pinfunction "TP_TP") (pintype "input"))
      (node (ref "CANH_4_C1") (pin "TP") (pinfunction "TP_TP") (pintype "input"))
      (node (ref "CANH_C1") (pin "TP") (pinfunction "TP_TP") (pintype "input"))
      (node (ref "S1") (pin "1") (pinfunction "1_1") (pintype "passive"))
    )
    (net (code "6") (name "/CANH_C3") (class "Default")
      (node (ref "CANH") (pin "TP") (pinfunction "TP_TP") (pintype "input"))
      (node (ref "CANH_1_C3") (pin "TP") (pinfunction "TP_TP") (pintype "input"))
      (node (ref "CANH_2_C3") (pin "TP") (pinfunction "TP_TP") (pintype "input"))
      (node (ref "CANH_3_C3") (pin "TP") (pinfunction "TP_TP") (pintype "input"))
      (node (ref "CANH_4_C3") (pin "TP") (pinfunction "TP_TP") (pintype "input"))
      (node (ref "CANH_C3") (pin "TP") (pinfunction "TP_TP") (pintype "input"))
    )
    (net (code "7") (name "/CANH_C4") (class "Default")
      (node (ref "CANH2") (pin "TP") (pinfunction "TP_TP") (pintype "input"))
      (node (ref "CANH_1_C4") (pin "TP") (pinfunction "TP_TP") (pintype "input"))
      (node (ref "CANH_2_C4") (pin "TP") (pinfunction "TP_TP") (pintype "input"))
      (node (ref "CANH_3_C4") (pin "TP") (pinfunction "TP_TP") (pintype "input"))
      (node (ref "CANH_4_C4") (pin "TP") (pinfunction "TP_TP") (pintype "input"))
    )
    (net (code "8") (name "/CANL") (class "Default")
      (node (ref "CANL_1_C1") (pin "TP") (pinfunction "TP_TP") (pintype "input"))
      (node (ref "CANL_2_C1") (pin "TP") (pinfunction "TP_TP") (pintype "input"))
      (node (ref "CANL_3_C1") (pin "TP") (pinfunction "TP_TP") (pintype "input"))
      (node (ref "CANL_4_C1") (pin "TP") (pinfunction "TP_TP") (pintype "input"))
      (node (ref "CANL_C1") (pin "TP") (pinfunction "TP_TP") (pintype "input"))
      (node (ref "R16") (pin "1") (pinfunction "1_1") (pintype "passive"))
      (node (ref "U$1") (pin "6") (pinfunction "CANL_6") (pintype "bidirectional"))
    )
    (net (code "9") (name "/CANL_C3") (class "Default")
      (node (ref "CANL") (pin "TP") (pinfunction "TP_TP") (pintype "input"))
      (node (ref "CANL_1_C3") (pin "TP") (pinfunction "TP_TP") (pintype "input"))
      (node (ref "CANL_2_C3") (pin "TP") (pinfunction "TP_TP") (pintype "input"))
      (node (ref "CANL_3_C3") (pin "TP") (pinfunction "TP_TP") (pintype "input"))
      (node (ref "CANL_4_C3") (pin "TP") (pinfunction "TP_TP") (pintype "input"))
      (node (ref "CANL_C3") (pin "TP") (pinfunction "TP_TP") (pintype "input"))
    )
    (net (code "10") (name "/CANL_C4") (class "Default")
      (node (ref "CANL2") (pin "TP") (pinfunction "TP_TP") (pintype "input"))
      (node (ref "CANL_1_C4") (pin "TP") (pinfunction "TP_TP") (pintype "input"))
      (node (ref "CANL_2_C4") (pin "TP") (pinfunction "TP_TP") (pintype "input"))
      (node (ref "CANL_3_C4") (pin "TP") (pinfunction "TP_TP") (pintype "input"))
      (node (ref "CANL_4_C4") (pin "TP") (pinfunction "TP_TP") (pintype "input"))
    )
    (net (code "11") (name "/CAN_RX") (class "Default")
      (node (ref "U$1") (pin "4") (pinfunction "R_4") (pintype "bidirectional"))
      (node (ref "U1") (pin "27") (pinfunction "P4.0/SCB0:SCL1_27") (pintype "bidirectional"))
    )
    (net (code "12") (name "/CAN_TX") (class "Default")
      (node (ref "U$1") (pin "1") (pinfunction "D_1") (pintype "bidirectional"))
      (node (ref "U1") (pin "28") (pinfunction "P4.1/SCB0:SDA1_28") (pintype "bidirectional"))
    )
    (net (code "13") (name "/CMOD") (class "Default")
      (node (ref "C4") (pin "1") (pinfunction "1_1") (pintype "passive"))
      (node (ref "R18") (pin "2") (pinfunction "2_2") (pintype "passive"))
      (node (ref "U1") (pin "29") (pinfunction "P4.2_29") (pintype "bidirectional"))
    )
    (net (code "14") (name "/CTANK") (class "Default")
      (node (ref "C5") (pin "1") (pinfunction "1_1") (pintype "passive"))
      (node (ref "U1") (pin "30") (pinfunction "P4.3_30") (pintype "bidirectional"))
    )
    (net (code "15") (name "/DN_1") (class "Default")
      (node (ref "DINA") (pin "1") (pinfunction "1_1") (pintype "passive"))
      (node (ref "S1") (pin "2") (pinfunction "2_2") (pintype "passive"))
    )
    (net (code "16") (name "/LED_S1") (class "Default")
      (node (ref "LED1") (pin "A") (pinfunction "A_A") (pintype "passive"))
      (node (ref "U1") (pin "4") (pinfunction "P2.2_4") (pintype "bidirectional"))
    )
    (net (code "17") (name "/LED_S2") (class "Default")
      (node (ref "L_C2") (pin "TP") (pinfunction "TP_TP") (pintype "input"))
      (node (ref "U1") (pin "5") (pinfunction "P2.3_5") (pintype "bidirectional"))
    )
    (net (code "18") (name "/LED_S2_C2") (class "Default")
      (node (ref "LED2") (pin "A") (pinfunction "A_A") (pintype "passive"))
      (node (ref "L_C2_C1") (pin "TP") (pinfunction "TP_TP") (pintype "input"))
    )
    (net (code "19") (name "/LED_S3") (class "Default")
      (node (ref "L_C3") (pin "TP") (pinfunction "TP_TP") (pintype "input"))
      (node (ref "U1") (pin "6") (pinfunction "P2.4_6") (pintype "bidirectional"))
    )
    (net (code "20") (name "/LED_S3_C3") (class "Default")
      (node (ref "LED3") (pin "A") (pinfunction "A_A") (pintype "passive"))
      (node (ref "L_C2_C3") (pin "TP") (pinfunction "TP_TP") (pintype "input"))
    )
    (net (code "21") (name "/LED_S4") (class "Default")
      (node (ref "L_C4") (pin "TP") (pinfunction "TP_TP") (pintype "input"))
      (node (ref "U1") (pin "7") (pinfunction "P2.5_7") (pintype "bidirectional"))
    )
    (net (code "22") (name "/LED_S4_C4") (class "Default")
      (node (ref "LED4") (pin "A") (pinfunction "A_A") (pintype "passive"))
      (node (ref "LEDC") (pin "TP") (pinfunction "TP_TP") (pintype "input"))
    )
    (net (code "23") (name "/LED_T_S4") (class "Default")
      (node (ref "LED") (pin "TP") (pinfunction "TP_TP") (pintype "input"))
      (node (ref "L_C2_C4") (pin "TP") (pinfunction "TP_TP") (pintype "input"))
    )
    (net (code "24") (name "/MOTOR") (class "Default")
      (node (ref "S1") (pin "3") (pinfunction "3_3") (pintype "passive"))
      (node (ref "U1") (pin "8") (pinfunction "P2.6_8") (pintype "bidirectional"))
      (node (ref "U1") (pin "9") (pinfunction "P2.7_9") (pintype "bidirectional"))
    )
    (net (code "25") (name "/P0_1") (class "Default")
      (node (ref "R11") (pin "1") (pinfunction "1_1") (pintype "passive"))
      (node (ref "U1") (pin "40") (pinfunction "P0.1/CAN1TX_40") (pintype "bidirectional"))
    )
    (net (code "26") (name "/P0_4") (class "Default")
      (node (ref "C8") (pin "1") (pinfunction "1_1") (pintype "passive"))
      (node (ref "CRYSTAL") (pin "2") (pinfunction "2_2") (pintype "passive"))
      (node (ref "U1") (pin "43") (pinfunction "P0.4_43") (pintype "bidirectional"))
    )
    (net (code "27") (name "/P0_5") (class "Default")
      (node (ref "C9") (pin "1") (pinfunction "1_1") (pintype "passive"))
      (node (ref "CRYSTAL") (pin "1") (pinfunction "1_1") (pintype "passive"))
      (node (ref "U1") (pin "44") (pinfunction "P0.5_44") (pintype "bidirectional"))
    )
    (net (code "28") (name "/SAR_BY") (class "Default")
      (node (ref "C6") (pin "1") (pinfunction "1_1") (pintype "passive"))
      (node (ref "U1") (pin "1") (pinfunction "P1.7/VREF_1") (pintype "bidirectional"))
    )
    (net (code "29") (name "/SCL_S1") (class "Default")
      (node (ref "R8") (pin "2") (pinfunction "2_2") (pintype "passive"))
      (node (ref "U1") (pin "2") (pinfunction "P2.0/SCB1:SCL1_2") (pintype "bidirectional"))
      (node (ref "U2") (pin "5") (pinfunction "SCL_5") (pintype "input"))
    )
    (net (code "30") (name "/SCL_S2") (class "Default")
      (node (ref "SCL_S2_C2") (pin "TP") (pinfunction "TP_TP") (pintype "input"))
      (node (ref "U1") (pin "51") (pinfunction "P5.0_51") (pintype "bidirectional"))
    )
    (net (code "31") (name "/SCL_S2_U") (class "Default")
      (node (ref "R10") (pin "2") (pinfunction "2_2") (pintype "passive"))
      (node (ref "SCL_S2_C2_C1") (pin "TP") (pinfunction "TP_TP") (pintype "input"))
      (node (ref "U3") (pin "5") (pinfunction "SCL_5") (pintype "input"))
    )
    (net (code "32") (name "/SCL_S3") (class "Default")
      (node (ref "SCL_S3_C3") (pin "TP") (pinfunction "TP_TP") (pintype "input"))
      (node (ref "U1") (pin "12") (pinfunction "P6.0/CAN0TX_EN_12") (pintype "bidirectional"))
    )
    (net (code "33") (name "/SCL_S3_U") (class "Default")
      (node (ref "R27") (pin "1") (pinfunction "1_1") (pintype "passive"))
      (node (ref "SCL_S3_C3_C2") (pin "TP") (pinfunction "TP_TP") (pintype "input"))
      (node (ref "U4") (pin "5") (pinfunction "SCL_5") (pintype "input"))
    )
    (net (code "34") (name "/SCL_S4") (class "Default")
      (node (ref "SCL_S4_C4") (pin "TP") (pinfunction "TP_TP") (pintype "input"))
      (node (ref "U1") (pin "58") (pinfunction "P1.0_58") (pintype "bidirectional"))
    )
    (net (code "35") (name "/SCL_S4_U") (class "Default")
      (node (ref "SCL") (pin "TP") (pinfunction "TP_TP") (pintype "input"))
      (node (ref "SCL_S4_C4_C2") (pin "TP") (pinfunction "TP_TP") (pintype "input"))
    )
    (net (code "36") (name "/SCL_S4_U_1") (class "Default")
      (node (ref "R25") (pin "1") (pinfunction "1_1") (pintype "passive"))
      (node (ref "SCL2") (pin "TP") (pinfunction "TP_TP") (pintype "input"))
      (node (ref "U5") (pin "5") (pinfunction "SCL_5") (pintype "input"))
    )
    (net (code "37") (name "/SDA_S1") (class "Default")
      (node (ref "R6") (pin "2") (pinfunction "2_2") (pintype "passive"))
      (node (ref "U1") (pin "3") (pinfunction "P2.1/SCB1:SDA1_3") (pintype "bidirectional"))
      (node (ref "U2") (pin "4") (pinfunction "SDA_4") (pintype "bidirectional"))
    )
    (net (code "38") (name "/SDA_S2") (class "Default")
      (node (ref "SDA_S2_C1") (pin "TP") (pinfunction "TP_TP") (pintype "input"))
      (node (ref "U1") (pin "52") (pinfunction "P5.1_52") (pintype "bidirectional"))
    )
    (net (code "39") (name "/SDA_S2_U") (class "Default")
      (node (ref "R12") (pin "2") (pinfunction "2_2") (pintype "passive"))
      (node (ref "SDA_S2_C2_C2") (pin "TP") (pinfunction "TP_TP") (pintype "input"))
      (node (ref "U3") (pin "4") (pinfunction "SDA_4") (pintype "bidirectional"))
    )
    (net (code "40") (name "/SDA_S3") (class "Default")
      (node (ref "SDA_S3_C1") (pin "TP") (pinfunction "TP_TP") (pintype "input"))
      (node (ref "U1") (pin "13") (pinfunction "P6.1/CAN0RX_13") (pintype "bidirectional"))
    )
    (net (code "41") (name "/SDA_S3_U") (class "Default")
      (node (ref "R26") (pin "1") (pinfunction "1_1") (pintype "passive"))
      (node (ref "SDA_S3_C3_C4") (pin "TP") (pinfunction "TP_TP") (pintype "input"))
      (node (ref "U4") (pin "4") (pinfunction "SDA_4") (pintype "bidirectional"))
    )
    (net (code "42") (name "/SDA_S4") (class "Default")
      (node (ref "SDA_S4_C1") (pin "TP") (pinfunction "TP_TP") (pintype "input"))
      (node (ref "U1") (pin "59") (pinfunction "P1.1_59") (pintype "bidirectional"))
    )
    (net (code "43") (name "/SDA_S4_U") (class "Default")
      (node (ref "SDA") (pin "TP") (pinfunction "TP_TP") (pintype "input"))
      (node (ref "SDA_S4_C4_C4") (pin "TP") (pinfunction "TP_TP") (pintype "input"))
    )
    (net (code "44") (name "/SDA_S4_U_1") (class "Default")
      (node (ref "R24") (pin "1") (pinfunction "1_1") (pintype "passive"))
      (node (ref "SDA2") (pin "TP") (pinfunction "TP_TP") (pintype "input"))
      (node (ref "U5") (pin "4") (pinfunction "SDA_4") (pintype "bidirectional"))
    )
    (net (code "45") (name "/SWDCLK") (class "Default")
      (node (ref "R2") (pin "2") (pinfunction "2_2") (pintype "passive"))
      (node (ref "U1") (pin "21") (pinfunction "P3.3_21") (pintype "bidirectional"))
    )
    (net (code "46") (name "/SWDIO") (class "Default")
      (node (ref "R3") (pin "2") (pinfunction "2_2") (pintype "passive"))
      (node (ref "U1") (pin "20") (pinfunction "P3.2_20") (pintype "bidirectional"))
    )
    (net (code "47") (name "/UART_RX") (class "Default")
      (node (ref "U1") (pin "37") (pinfunction "P7.0/SCB3:SCL1_37") (pintype "bidirectional"))
    )
    (net (code "48") (name "/UART_TX") (class "Default")
      (node (ref "U1") (pin "38") (pinfunction "P7.1/SCB3:SDA1_38") (pintype "bidirectional"))
    )
    (net (code "49") (name "/VCCC") (class "Default")
      (node (ref "C1") (pin "+") (pinfunction "+_+") (pintype "passive"))
      (node (ref "DINA") (pin "2") (pinfunction "2_2") (pintype "passive"))
      (node (ref "VCC_1_C1") (pin "TP") (pinfunction "TP_TP") (pintype "input"))
      (node (ref "VCC_2_C1") (pin "TP") (pinfunction "TP_TP") (pintype "input"))
      (node (ref "VCC_3_C1") (pin "TP") (pinfunction "TP_TP") (pintype "input"))
      (node (ref "VCC_4_C1") (pin "TP") (pinfunction "TP_TP") (pintype "input"))
      (node (ref "VCC_C1") (pin "TP") (pinfunction "TP_TP") (pintype "input"))
    )
    (net (code "50") (name "/VCCD") (class "Default")
      (node (ref "C7") (pin "1") (pinfunction "1_1") (pintype "passive"))
      (node (ref "U1") (pin "48") (pinfunction "VCCD_48") (pintype "bidirectional"))
    )
    (net (code "51") (name "/VCC_C2") (class "Default")
      (node (ref "U$2") (pin "IN+") (pinfunction "IN+_IN+") (pintype "bidirectional"))
      (node (ref "VCC_1_C2") (pin "TP") (pinfunction "TP_TP") (pintype "input"))
      (node (ref "VCC_2_C2") (pin "TP") (pinfunction "TP_TP") (pintype "input"))
      (node (ref "VCC_3_C2") (pin "TP") (pinfunction "TP_TP") (pintype "input"))
      (node (ref "VCC_4_C2") (pin "TP") (pinfunction "TP_TP") (pintype "input"))
      (node (ref "VCC_C2") (pin "TP") (pinfunction "TP_TP") (pintype "input"))
      (node (ref "VCC_C2_C3") (pin "TP") (pinfunction "TP_TP") (pintype "input"))
    )
    (net (code "52") (name "/VCC_C3") (class "Default")
      (node (ref "VCC") (pin "TP") (pinfunction "TP_TP") (pintype "input"))
      (node (ref "VCC_1_C3") (pin "TP") (pinfunction "TP_TP") (pintype "input"))
      (node (ref "VCC_2_C3") (pin "TP") (pinfunction "TP_TP") (pintype "input"))
      (node (ref "VCC_3_C3") (pin "TP") (pinfunction "TP_TP") (pintype "input"))
      (node (ref "VCC_4_C3") (pin "TP") (pinfunction "TP_TP") (pintype "input"))
      (node (ref "VCC_C3") (pin "TP") (pinfunction "TP_TP") (pintype "input"))
    )
    (net (code "53") (name "/VCC_C4") (class "Default")
      (node (ref "BATTERY+") (pin "TP") (pinfunction "TP_TP") (pintype "input"))
      (node (ref "C2") (pin "+") (pinfunction "+_+") (pintype "passive"))
      (node (ref "D1") (pin "C") (pinfunction "C_C") (pintype "passive"))
      (node (ref "VCC2") (pin "TP") (pinfunction "TP_TP") (pintype "input"))
      (node (ref "VCC_1_C4") (pin "TP") (pinfunction "TP_TP") (pintype "input"))
      (node (ref "VCC_2_C4") (pin "TP") (pinfunction "TP_TP") (pintype "input"))
      (node (ref "VCC_3_C4") (pin "TP") (pinfunction "TP_TP") (pintype "input"))
      (node (ref "VCC_4_C4") (pin "TP") (pinfunction "TP_TP") (pintype "input"))
    )
    (net (code "54") (name "/VDDA") (class "Default")
      (node (ref "U1") (pin "11") (pinfunction "VDDA1_11") (pintype "bidirectional"))
      (node (ref "U1") (pin "56") (pinfunction "VDDA2_56") (pintype "bidirectional"))
      (node (ref "VDDA_C1") (pin "TP") (pinfunction "TP_TP") (pintype "input"))
    )
    (net (code "55") (name "/VDDA2") (class "Default")
      (node (ref "L1") (pin "2") (pinfunction "2_2") (pintype "passive"))
      (node (ref "VDDA_C2") (pin "TP") (pinfunction "TP_TP") (pintype "input"))
    )
    (net (code "56") (name "/VDDD") (class "Default")
      (node (ref "U1") (pin "50") (pinfunction "VDDD_50") (pintype "bidirectional"))
      (node (ref "VDDD_C1") (pin "TP") (pinfunction "TP_TP") (pintype "input"))
    )
    (net (code "57") (name "/VDDD2") (class "Default")
      (node (ref "L2") (pin "2") (pinfunction "2_2") (pintype "passive"))
      (node (ref "VDDD_C2") (pin "TP") (pinfunction "TP_TP") (pintype "input"))
    )
    (net (code "58") (name "/VDDIO") (class "Default")
      (node (ref "U1") (pin "26") (pinfunction "VDDIO_26") (pintype "bidirectional"))
      (node (ref "VDDIO_C1") (pin "TP") (pinfunction "TP_TP") (pintype "input"))
    )
    (net (code "59") (name "/VDDIO2") (class "Default")
      (node (ref "R15") (pin "2") (pinfunction "2_2") (pintype "passive"))
      (node (ref "VDDIO_C2") (pin "TP") (pinfunction "TP_TP") (pintype "input"))
    )
    (net (code "60") (name "/XRES") (class "Default")
      (node (ref "C10") (pin "1") (pinfunction "1_1") (pintype "passive"))
      (node (ref "R1") (pin "2") (pinfunction "2_2") (pintype "passive"))
      (node (ref "R14") (pin "2") (pinfunction "2_2") (pintype "passive"))
      (node (ref "U1") (pin "47") (pinfunction "XRES_47") (pintype "bidirectional"))
    )
    (net (code "61") (name "GND1") (class "Default")
      (node (ref "C1") (pin "-") (pinfunction "-_-") (pintype "passive"))
      (node (ref "C10") (pin "2") (pinfunction "2_2") (pintype "passive"))
      (node (ref "C4") (pin "2") (pinfunction "2_2") (pintype "passive"))
      (node (ref "C5") (pin "2") (pinfunction "2_2") (pintype "passive"))
      (node (ref "C6") (pin "2") (pinfunction "2_2") (pintype "passive"))
      (node (ref "C7") (pin "2") (pinfunction "2_2") (pintype "passive"))
      (node (ref "C8") (pin "2") (pinfunction "2_2") (pintype "passive"))
      (node (ref "C9") (pin "2") (pinfunction "2_2") (pintype "passive"))
      (node (ref "CN1") (pin "D-") (pinfunction "D-_D-") (pintype "bidirectional"))
      (node (ref "DINA") (pin "3") (pinfunction "3_3") (pintype "passive"))
      (node (ref "GND_1_C1") (pin "TP") (pinfunction "TP_TP") (pintype "input"))
      (node (ref "GND_2_C1") (pin "TP") (pinfunction "TP_TP") (pintype "input"))
      (node (ref "GND_3_C1") (pin "TP") (pinfunction "TP_TP") (pintype "input"))
      (node (ref "GND_4_C1") (pin "TP") (pinfunction "TP_TP") (pintype "input"))
      (node (ref "GND_C1") (pin "TP") (pinfunction "TP_TP") (pintype "input"))
      (node (ref "R13") (pin "1") (pinfunction "1_1") (pintype "passive"))
      (node (ref "R17") (pin "2") (pinfunction "2_2") (pintype "passive"))
      (node (ref "R18") (pin "1") (pinfunction "1_1") (pintype "passive"))
      (node (ref "R19") (pin "2") (pinfunction "2_2") (pintype "passive"))
      (node (ref "R4") (pin "2") (pinfunction "2_2") (pintype "passive"))
      (node (ref "U$1") (pin "2") (pinfunction "GND_2") (pintype "power_in"))
      (node (ref "U1") (pin "10") (pinfunction "VSSA1_10") (pintype "bidirectional"))
      (node (ref "U1") (pin "17") (pinfunction "VSSIO_17") (pintype "bidirectional"))
      (node (ref "U1") (pin "49") (pinfunction "VSSD_49") (pintype "bidirectional"))
      (node (ref "U1") (pin "57") (pinfunction "VSSA2_57") (pintype "bidirectional"))
      (node (ref "U2") (pin "12") (pinfunction "GND_12") (pintype "power_in"))
      (node (ref "U2") (pin "13") (pinfunction "GND_13") (pintype "power_in"))
    )
    (net (code "62") (name "GND2") (class "Default")
      (node (ref "GND_1_C2") (pin "TP") (pinfunction "TP_TP") (pintype "input"))
      (node (ref "GND_2_C2") (pin "TP") (pinfunction "TP_TP") (pintype "input"))
      (node (ref "GND_3_C2") (pin "TP") (pinfunction "TP_TP") (pintype "input"))
      (node (ref "GND_4_C2") (pin "TP") (pinfunction "TP_TP") (pintype "input"))
      (node (ref "GND_C2") (pin "TP") (pinfunction "TP_TP") (pintype "input"))
      (node (ref "GND_C2_C3") (pin "TP") (pinfunction "TP_TP") (pintype "input"))
      (node (ref "R20") (pin "2") (pinfunction "2_2") (pintype "passive"))
      (node (ref "R23") (pin "2") (pinfunction "2_2") (pintype "passive"))
      (node (ref "R5") (pin "1") (pinfunction "1_1") (pintype "passive"))
      (node (ref "U$2") (pin "IN-") (pinfunction "IN-_IN-") (pintype "bidirectional"))
      (node (ref "U$2") (pin "OUT-") (pinfunction "OUT-_OUT-") (pintype "bidirectional"))
      (node (ref "U3") (pin "12") (pinfunction "GND_12") (pintype "power_in"))
      (node (ref "U3") (pin "13") (pinfunction "GND_13") (pintype "power_in"))
    )
    (net (code "63") (name "GND3") (class "Default")
      (node (ref "GND") (pin "TP") (pinfunction "TP_TP") (pintype "input"))
      (node (ref "GND_1_C3") (pin "TP") (pinfunction "TP_TP") (pintype "input"))
      (node (ref "GND_2_C3") (pin "TP") (pinfunction "TP_TP") (pintype "input"))
      (node (ref "GND_3_C3") (pin "TP") (pinfunction "TP_TP") (pintype "input"))
      (node (ref "GND_4_C3") (pin "TP") (pinfunction "TP_TP") (pintype "input"))
      (node (ref "GND_C3") (pin "TP") (pinfunction "TP_TP") (pintype "input"))
      (node (ref "R21") (pin "2") (pinfunction "2_2") (pintype "passive"))
      (node (ref "R7") (pin "1") (pinfunction "1_1") (pintype "passive"))
      (node (ref "U4") (pin "12") (pinfunction "GND_12") (pintype "power_in"))
      (node (ref "U4") (pin "13") (pinfunction "GND_13") (pintype "power_in"))
    )
    (net (code "64") (name "GND4") (class "Default")
      (node (ref "BATTERY-") (pin "TP") (pinfunction "TP_TP") (pintype "input"))
      (node (ref "C2") (pin "-") (pinfunction "-_-") (pintype "passive"))
      (node (ref "D1") (pin "A") (pinfunction "A_A") (pintype "passive"))
      (node (ref "GND2") (pin "TP") (pinfunction "TP_TP") (pintype "input"))
      (node (ref "GND_1_C4") (pin "TP") (pinfunction "TP_TP") (pintype "input"))
      (node (ref "GND_2_C4") (pin "TP") (pinfunction "TP_TP") (pintype "input"))
      (node (ref "GND_3_C4") (pin "TP") (pinfunction "TP_TP") (pintype "input"))
      (node (ref "GND_4_C4") (pin "TP") (pinfunction "TP_TP") (pintype "input"))
      (node (ref "R22") (pin "2") (pinfunction "2_2") (pintype "passive"))
      (node (ref "R9") (pin "1") (pinfunction "1_1") (pintype "passive"))
      (node (ref "U5") (pin "12") (pinfunction "GND_12") (pintype "power_in"))
      (node (ref "U5") (pin "13") (pinfunction "GND_13") (pintype "power_in"))
    )
    (net (code "65") (name "Net-(CANH_1_C2-PadTP)") (class "Default")
      (node (ref "CANH_1_C2") (pin "TP") (pinfunction "TP_TP") (pintype "input"))
      (node (ref "CANH_2_C2") (pin "TP") (pinfunction "TP_TP") (pintype "input"))
      (node (ref "CANH_3_C2") (pin "TP") (pinfunction "TP_TP") (pintype "input"))
      (node (ref "CANH_4_C2") (pin "TP") (pinfunction "TP_TP") (pintype "input"))
      (node (ref "CANH_C2") (pin "TP") (pinfunction "TP_TP") (pintype "input"))
      (node (ref "CANH_C2_C3") (pin "TP") (pinfunction "TP_TP") (pintype "input"))
    )
    (net (code "66") (name "Net-(CANL_1_C2-PadTP)") (class "Default")
      (node (ref "CANL_1_C2") (pin "TP") (pinfunction "TP_TP") (pintype "input"))
      (node (ref "CANL_2_C2") (pin "TP") (pinfunction "TP_TP") (pintype "input"))
      (node (ref "CANL_3_C2") (pin "TP") (pinfunction "TP_TP") (pintype "input"))
      (node (ref "CANL_4_C2") (pin "TP") (pinfunction "TP_TP") (pintype "input"))
      (node (ref "CANL_C2") (pin "TP") (pinfunction "TP_TP") (pintype "input"))
      (node (ref "CANL_C2_C3") (pin "TP") (pinfunction "TP_TP") (pintype "input"))
    )
    (net (code "67") (name "Net-(CN1-PadD+)") (class "Default")
      (node (ref "CN1") (pin "D+") (pinfunction "D+_D+") (pintype "bidirectional"))
      (node (ref "R1") (pin "1") (pinfunction "1_1") (pintype "passive"))
    )
    (net (code "68") (name "Net-(CN1-PadGND)") (class "Default")
      (node (ref "CN1") (pin "GND") (pinfunction "GND_GND") (pintype "power_in"))
      (node (ref "R3") (pin "1") (pinfunction "1_1") (pintype "passive"))
    )
    (net (code "69") (name "Net-(CN1-PadID)") (class "Default")
      (node (ref "CN1") (pin "ID") (pinfunction "ID_ID") (pintype "bidirectional"))
      (node (ref "R2") (pin "1") (pinfunction "1_1") (pintype "passive"))
    )
    (net (code "70") (name "Net-(D2-PadA)") (class "Default")
      (node (ref "D2") (pin "A") (pinfunction "A_A") (pintype "passive"))
      (node (ref "D3") (pin "A") (pinfunction "A_A") (pintype "passive"))
      (node (ref "U$2") (pin "OUT+") (pinfunction "OUT+_OUT+") (pintype "bidirectional"))
    )
    (net (code "71") (name "Net-(LED1-PadC)") (class "Default")
      (node (ref "LED1") (pin "C") (pinfunction "C_C") (pintype "passive"))
      (node (ref "R19") (pin "1") (pinfunction "1_1") (pintype "passive"))
    )
    (net (code "72") (name "Net-(LED2-PadC)") (class "Default")
      (node (ref "LED2") (pin "C") (pinfunction "C_C") (pintype "passive"))
      (node (ref "R20") (pin "1") (pinfunction "1_1") (pintype "passive"))
    )
    (net (code "73") (name "Net-(LED3-PadC)") (class "Default")
      (node (ref "LED3") (pin "C") (pinfunction "C_C") (pintype "passive"))
      (node (ref "R21") (pin "1") (pinfunction "1_1") (pintype "passive"))
    )
    (net (code "74") (name "Net-(LED4-PadC)") (class "Default")
      (node (ref "LED4") (pin "C") (pinfunction "C_C") (pintype "passive"))
      (node (ref "R22") (pin "1") (pinfunction "1_1") (pintype "passive"))
    )
    (net (code "75") (name "Net-(LED5-PadC)") (class "Default")
      (node (ref "LED5") (pin "C") (pinfunction "C_C") (pintype "passive"))
      (node (ref "R23") (pin "1") (pinfunction "1_1") (pintype "passive"))
    )
    (net (code "76") (name "Net-(L_C1_C3-PadTP)") (class "Default")
      (node (ref "L_C1_C3") (pin "TP") (pinfunction "TP_TP") (pintype "input"))
      (node (ref "L_C3_C2") (pin "TP") (pinfunction "TP_TP") (pintype "input"))
    )
    (net (code "77") (name "Net-(L_C1_C4-PadTP)") (class "Default")
      (node (ref "L_C1_C4") (pin "TP") (pinfunction "TP_TP") (pintype "input"))
      (node (ref "L_C4_C1") (pin "TP") (pinfunction "TP_TP") (pintype "input"))
    )
    (net (code "78") (name "Net-(R4-Pad1)") (class "Default")
      (node (ref "R4") (pin "1") (pinfunction "1_1") (pintype "passive"))
      (node (ref "U2") (pin "2") (pinfunction "IR_CA_2") (pintype "power_in"))
      (node (ref "U2") (pin "3") (pinfunction "IR_CA_3") (pintype "power_in"))
    )
    (net (code "79") (name "Net-(R5-Pad2)") (class "Default")
      (node (ref "R5") (pin "2") (pinfunction "2_2") (pintype "passive"))
      (node (ref "U3") (pin "2") (pinfunction "IR_CA_2") (pintype "power_in"))
      (node (ref "U3") (pin "3") (pinfunction "IR_CA_3") (pintype "power_in"))
    )
    (net (code "80") (name "Net-(R7-Pad2)") (class "Default")
      (node (ref "R7") (pin "2") (pinfunction "2_2") (pintype "passive"))
      (node (ref "U4") (pin "2") (pinfunction "IR_CA_2") (pintype "power_in"))
      (node (ref "U4") (pin "3") (pinfunction "IR_CA_3") (pintype "power_in"))
    )
    (net (code "81") (name "Net-(R9-Pad2)") (class "Default")
      (node (ref "R9") (pin "2") (pinfunction "2_2") (pintype "passive"))
      (node (ref "U5") (pin "2") (pinfunction "IR_CA_2") (pintype "power_in"))
      (node (ref "U5") (pin "3") (pinfunction "IR_CA_3") (pintype "power_in"))
    )
    (net (code "82") (name "Net-(R11-Pad2)") (class "Default")
      (node (ref "R11") (pin "2") (pinfunction "2_2") (pintype "passive"))
      (node (ref "R13") (pin "2") (pinfunction "2_2") (pintype "passive"))
    )
    (net (code "83") (name "Net-(SCL_S3_C1_C3-PadTP)") (class "Default")
      (node (ref "SCL_S3_C1_C3") (pin "TP") (pinfunction "TP_TP") (pintype "input"))
      (node (ref "SCL_S3_C3_C1") (pin "TP") (pinfunction "TP_TP") (pintype "input"))
    )
    (net (code "84") (name "Net-(SCL_S4_C1_C4-PadTP)") (class "Default")
      (node (ref "SCL_S4_C1_C4") (pin "TP") (pinfunction "TP_TP") (pintype "input"))
      (node (ref "SCL_S4_C4_C1") (pin "TP") (pinfunction "TP_TP") (pintype "input"))
    )
    (net (code "85") (name "Net-(SDA_S3_C1_C1-PadTP)") (class "Default")
      (node (ref "SDA_S3_C1_C1") (pin "TP") (pinfunction "TP_TP") (pintype "input"))
      (node (ref "SDA_S3_C3_C3") (pin "TP") (pinfunction "TP_TP") (pintype "input"))
    )
    (net (code "86") (name "Net-(SDA_S4_C1_C1-PadTP)") (class "Default")
      (node (ref "SDA_S4_C1_C1") (pin "TP") (pinfunction "TP_TP") (pintype "input"))
      (node (ref "SDA_S4_C4_C3") (pin "TP") (pinfunction "TP_TP") (pintype "input"))
    )
    (net (code "87") (name "Net-(U$1-CANH)") (class "Default")
      (node (ref "R16") (pin "2") (pinfunction "2_2") (pintype "passive"))
      (node (ref "S1") (pin "4") (pinfunction "4_4") (pintype "passive"))
      (node (ref "U$1") (pin "7") (pinfunction "CANH_7") (pintype "bidirectional"))
    )
    (net (code "88") (name "Net-(U$1-RS)") (class "Default")
      (node (ref "R17") (pin "1") (pinfunction "1_1") (pintype "passive"))
      (node (ref "U$1") (pin "8") (pinfunction "RS_8") (pintype "bidirectional"))
    )
    (net (code "89") (name "unconnected-(MECH_LINK_1-PadTP)") (class "Default")
      (node (ref "MECH_LINK_1") (pin "TP") (pinfunction "TP_TP") (pintype "input"))
    )
    (net (code "90") (name "unconnected-(MECH_LINK_2-PadTP)") (class "Default")
      (node (ref "MECH_LINK_2") (pin "TP") (pinfunction "TP_TP") (pintype "input"))
    )
    (net (code "91") (name "unconnected-(MECH_LINK_3-PadTP)") (class "Default")
      (node (ref "MECH_LINK_3") (pin "TP") (pinfunction "TP_TP") (pintype "input"))
    )
    (net (code "92") (name "unconnected-(MECH_LINK_4-PadTP)") (class "Default")
      (node (ref "MECH_LINK_4") (pin "TP") (pinfunction "TP_TP") (pintype "input"))
    )
    (net (code "93") (name "unconnected-(MECH_LINK_5-PadTP)") (class "Default")
      (node (ref "MECH_LINK_5") (pin "TP") (pinfunction "TP_TP") (pintype "input"))
    )
    (net (code "94") (name "unconnected-(MECH_LINK_6-PadTP)") (class "Default")
      (node (ref "MECH_LINK_6") (pin "TP") (pinfunction "TP_TP") (pintype "input"))
    )
    (net (code "95") (name "unconnected-(MECH_LINK_7-PadTP)") (class "Default")
      (node (ref "MECH_LINK_7") (pin "TP") (pinfunction "TP_TP") (pintype "input"))
    )
    (net (code "96") (name "unconnected-(MECH_LINK_8-PadTP)") (class "Default")
      (node (ref "MECH_LINK_8") (pin "TP") (pinfunction "TP_TP") (pintype "input"))
    )
    (net (code "97") (name "unconnected-(MECH_LINK_9-PadTP)") (class "Default")
      (node (ref "MECH_LINK_9") (pin "TP") (pinfunction "TP_TP") (pintype "input"))
    )
    (net (code "98") (name "unconnected-(MECH_LINK_11-PadTP)") (class "Default")
      (node (ref "MECH_LINK_11") (pin "TP") (pinfunction "TP_TP") (pintype "input"))
    )
    (net (code "99") (name "unconnected-(U$1-VREF-Pad5)") (class "Default")
      (node (ref "U$1") (pin "5") (pinfunction "VREF_5") (pintype "bidirectional"))
    )
    (net (code "100") (name "unconnected-(U1-NC1-Pad34)") (class "Default")
      (node (ref "U1") (pin "34") (pinfunction "NC1_34") (pintype "bidirectional"))
    )
    (net (code "101") (name "unconnected-(U1-NC2-Pad35)") (class "Default")
      (node (ref "U1") (pin "35") (pinfunction "NC2_35") (pintype "bidirectional"))
    )
    (net (code "102") (name "unconnected-(U1-NC3-Pad36)") (class "Default")
      (node (ref "U1") (pin "36") (pinfunction "NC3_36") (pintype "bidirectional"))
    )
    (net (code "103") (name "unconnected-(U1-P0.0{slash}CAN1RX-Pad39)") (class "Default")
      (node (ref "U1") (pin "39") (pinfunction "P0.0/CAN1RX_39") (pintype "bidirectional"))
    )
    (net (code "104") (name "unconnected-(U1-P0.2-Pad41)") (class "Default")
      (node (ref "U1") (pin "41") (pinfunction "P0.2_41") (pintype "bidirectional"))
    )
    (net (code "105") (name "unconnected-(U1-P0.3-Pad42)") (class "Default")
      (node (ref "U1") (pin "42") (pinfunction "P0.3_42") (pintype "bidirectional"))
    )
    (net (code "106") (name "unconnected-(U1-P0.6-Pad45)") (class "Default")
      (node (ref "U1") (pin "45") (pinfunction "P0.6_45") (pintype "bidirectional"))
    )
    (net (code "107") (name "unconnected-(U1-P0.7{slash}CAN1TX_EN-Pad46)") (class "Default")
      (node (ref "U1") (pin "46") (pinfunction "P0.7/CAN1TX_EN_46") (pintype "bidirectional"))
    )
    (net (code "108") (name "unconnected-(U1-P1.2-Pad60)") (class "Default")
      (node (ref "U1") (pin "60") (pinfunction "P1.2_60") (pintype "bidirectional"))
    )
    (net (code "109") (name "unconnected-(U1-P1.3-Pad61)") (class "Default")
      (node (ref "U1") (pin "61") (pinfunction "P1.3_61") (pintype "bidirectional"))
    )
    (net (code "110") (name "unconnected-(U1-P1.4-Pad62)") (class "Default")
      (node (ref "U1") (pin "62") (pinfunction "P1.4_62") (pintype "bidirectional"))
    )
    (net (code "111") (name "unconnected-(U1-P1.5-Pad63)") (class "Default")
      (node (ref "U1") (pin "63") (pinfunction "P1.5_63") (pintype "bidirectional"))
    )
    (net (code "112") (name "unconnected-(U1-P1.6-Pad64)") (class "Default")
      (node (ref "U1") (pin "64") (pinfunction "P1.6_64") (pintype "bidirectional"))
    )
    (net (code "113") (name "unconnected-(U1-P3.0{slash}SCB1:RX-Pad18)") (class "Default")
      (node (ref "U1") (pin "18") (pinfunction "P3.0/SCB1:RX_18") (pintype "bidirectional"))
    )
    (net (code "114") (name "unconnected-(U1-P3.1{slash}SCB1:TX-Pad19)") (class "Default")
      (node (ref "U1") (pin "19") (pinfunction "P3.1/SCB1:TX_19") (pintype "bidirectional"))
    )
    (net (code "115") (name "unconnected-(U1-P3.4-Pad22)") (class "Default")
      (node (ref "U1") (pin "22") (pinfunction "P3.4_22") (pintype "bidirectional"))
    )
    (net (code "116") (name "unconnected-(U1-P3.5-Pad23)") (class "Default")
      (node (ref "U1") (pin "23") (pinfunction "P3.5_23") (pintype "bidirectional"))
    )
    (net (code "117") (name "unconnected-(U1-P3.6-Pad24)") (class "Default")
      (node (ref "U1") (pin "24") (pinfunction "P3.6_24") (pintype "bidirectional"))
    )
    (net (code "118") (name "unconnected-(U1-P3.7-Pad25)") (class "Default")
      (node (ref "U1") (pin "25") (pinfunction "P3.7_25") (pintype "bidirectional"))
    )
    (net (code "119") (name "unconnected-(U1-P4.4-Pad31)") (class "Default")
      (node (ref "U1") (pin "31") (pinfunction "P4.4_31") (pintype "bidirectional"))
    )
    (net (code "120") (name "unconnected-(U1-P4.5-Pad32)") (class "Default")
      (node (ref "U1") (pin "32") (pinfunction "P4.5_32") (pintype "bidirectional"))
    )
    (net (code "121") (name "unconnected-(U1-P4.6-Pad33)") (class "Default")
      (node (ref "U1") (pin "33") (pinfunction "P4.6_33") (pintype "bidirectional"))
    )
    (net (code "122") (name "unconnected-(U1-P5.2-Pad53)") (class "Default")
      (node (ref "U1") (pin "53") (pinfunction "P5.2_53") (pintype "bidirectional"))
    )
    (net (code "123") (name "unconnected-(U1-P5.3-Pad54)") (class "Default")
      (node (ref "U1") (pin "54") (pinfunction "P5.3_54") (pintype "bidirectional"))
    )
    (net (code "124") (name "unconnected-(U1-P5.5-Pad55)") (class "Default")
      (node (ref "U1") (pin "55") (pinfunction "P5.5_55") (pintype "bidirectional"))
    )
    (net (code "125") (name "unconnected-(U1-P6.2{slash}CAN0TX-Pad14)") (class "Default")
      (node (ref "U1") (pin "14") (pinfunction "P6.2/CAN0TX_14") (pintype "bidirectional"))
    )
    (net (code "126") (name "unconnected-(U1-P6.4-Pad15)") (class "Default")
      (node (ref "U1") (pin "15") (pinfunction "P6.4_15") (pintype "bidirectional"))
    )
    (net (code "127") (name "unconnected-(U1-P6.5-Pad16)") (class "Default")
      (node (ref "U1") (pin "16") (pinfunction "P6.5_16") (pintype "bidirectional"))
    )
    (net (code "128") (name "unconnected-(U2-INT-Pad6)") (class "Default")
      (node (ref "U2") (pin "6") (pinfunction "INT_6") (pintype "output"))
    )
    (net (code "129") (name "unconnected-(U3-INT-Pad6)") (class "Default")
      (node (ref "U3") (pin "6") (pinfunction "INT_6") (pintype "output"))
    )
    (net (code "130") (name "unconnected-(U4-INT-Pad6)") (class "Default")
      (node (ref "U4") (pin "6") (pinfunction "INT_6") (pintype "output"))
    )
    (net (code "131") (name "unconnected-(U5-INT-Pad6)") (class "Default")
      (node (ref "U5") (pin "6") (pinfunction "INT_6") (pintype "output"))
    )
  )
)
